# Connectors.net
KiCad netlist of a schematic drawn in Altium Designer
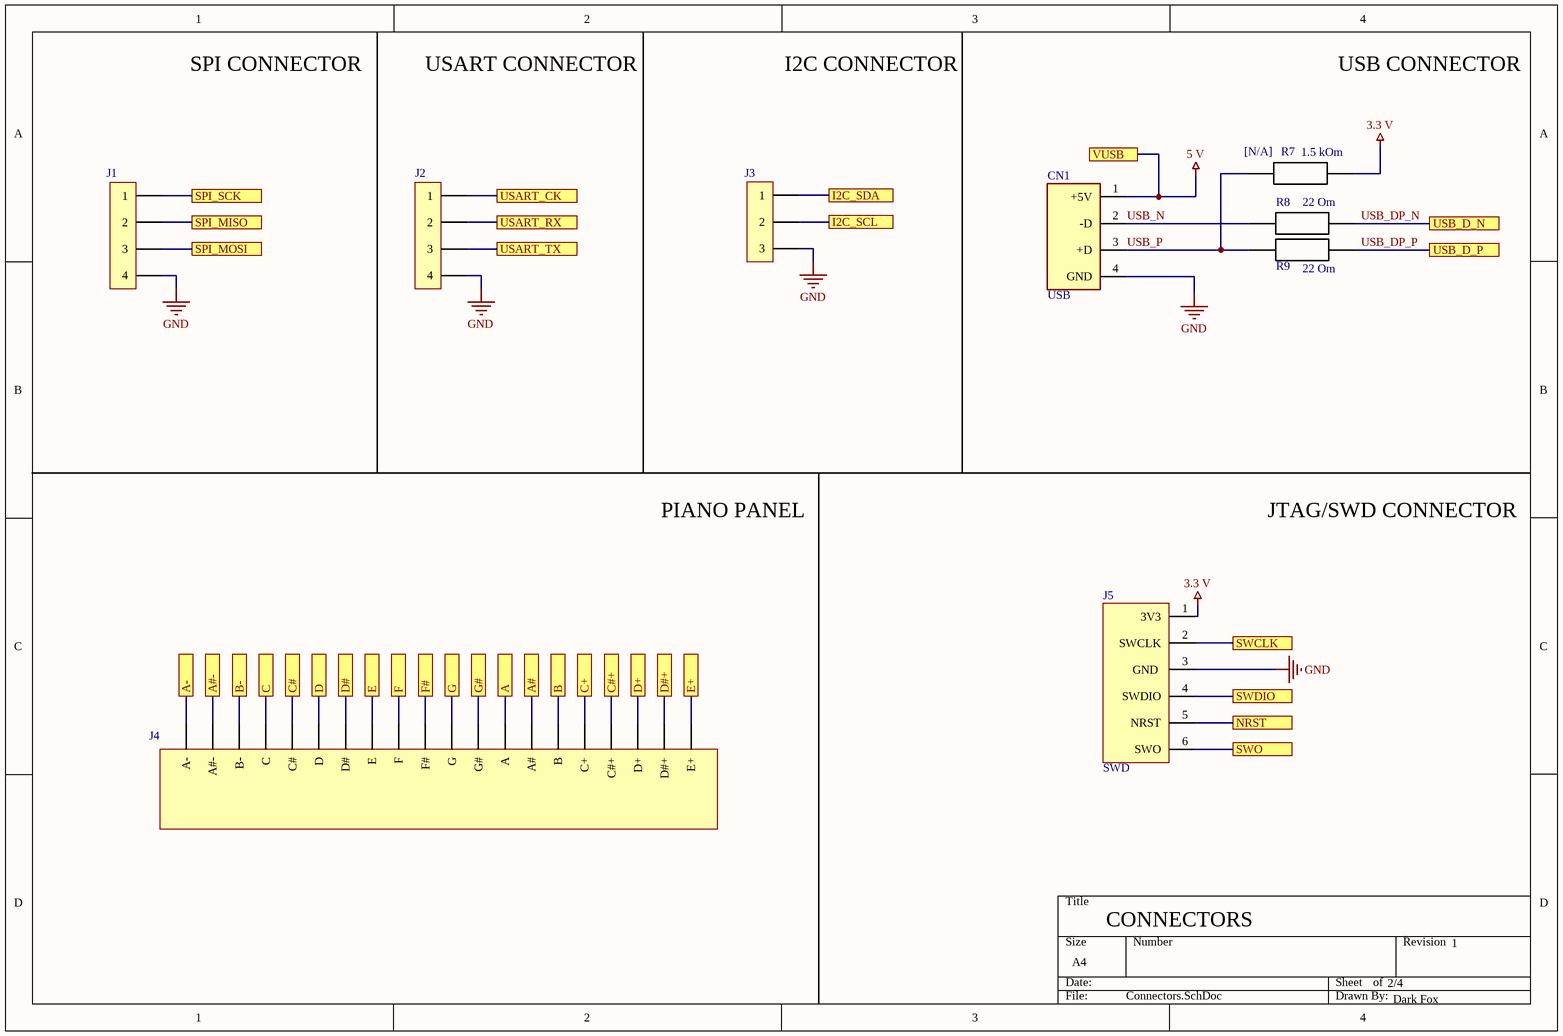
[diagram p0: Connectors.SchDoc]

(export (version "E")
  (design (tool "Eeschema 10.0.6"))
  (components
    (comp (ref "CN1") (value "USB") (footprint "USB") (libsource (lib "MyLib") (part "USB_2")))
    (comp (ref "J1") (value "4x2.54") (footprint "SMD 4x2.54") (libsource (lib "MyLib") (part "4x2.54")))
    (comp (ref "J2") (value "4x2.54") (footprint "SMD 4x2.54") (libsource (lib "MyLib") (part "4x2.54")))
    (comp (ref "J3") (value "3x2.54") (footprint "SMD 3x2.54") (libsource (lib "MyLib") (part "3x2.54")))
    (comp (ref "J4")
      (value "piano_full")
      (footprint "PIANO_FULL")
      (libsource (lib "MyLib") (part "piano_full"))
    )
    (comp (ref "J5") (value "SWD") (footprint "SWD_6_2.54") (libsource (lib "MyLib") (part "SWD")))
    (comp (ref "R7") (value "1.5 kOm") (footprint "1206") (libsource (lib "MyLib") (part "Res")))
    (comp (ref "R8") (value "22 Om") (footprint "1206") (libsource (lib "MyLib") (part "Res")))
    (comp (ref "R9") (value "22 Om") (footprint "1206") (libsource (lib "MyLib") (part "Res")))
  )
  (nets
    (net (code "1") (name "/A") (class "Default")
      (node (ref "J4") (pin "13") (pinfunction "A_13") (pintype "passive"))
    )
    (net (code "2") (name "/A#") (class "Default")
      (node (ref "J4") (pin "14") (pinfunction "A#_14") (pintype "passive"))
    )
    (net (code "3") (name "/A#-") (class "Default")
      (node (ref "J4") (pin "2") (pinfunction "A#-_2") (pintype "passive"))
    )
    (net (code "4") (name "/A-") (class "Default")
      (node (ref "J4") (pin "1") (pinfunction "A-_1") (pintype "passive"))
    )
    (net (code "5") (name "/B") (class "Default")
      (node (ref "J4") (pin "15") (pinfunction "B_15") (pintype "passive"))
    )
    (net (code "6") (name "/B-") (class "Default")
      (node (ref "J4") (pin "3") (pinfunction "B-_3") (pintype "passive"))
    )
    (net (code "7") (name "/C") (class "Default")
      (node (ref "J4") (pin "4") (pinfunction "C_4") (pintype "passive"))
    )
    (net (code "8") (name "/C#") (class "Default")
      (node (ref "J4") (pin "5") (pinfunction "C#_5") (pintype "passive"))
    )
    (net (code "9") (name "/C#+") (class "Default")
      (node (ref "J4") (pin "17") (pinfunction "C#+_17") (pintype "passive"))
    )
    (net (code "10") (name "/C+") (class "Default")
      (node (ref "J4") (pin "16") (pinfunction "C+_16") (pintype "passive"))
    )
    (net (code "11") (name "/D") (class "Default")
      (node (ref "J4") (pin "6") (pinfunction "D_6") (pintype "passive"))
    )
    (net (code "12") (name "/D#") (class "Default")
      (node (ref "J4") (pin "7") (pinfunction "D#_7") (pintype "passive"))
    )
    (net (code "13") (name "/D#+") (class "Default")
      (node (ref "J4") (pin "19") (pinfunction "D#+_19") (pintype "passive"))
    )
    (net (code "14") (name "/D+") (class "Default")
      (node (ref "J4") (pin "18") (pinfunction "D+_18") (pintype "passive"))
    )
    (net (code "15") (name "/E") (class "Default")
      (node (ref "J4") (pin "8") (pinfunction "E_8") (pintype "passive"))
    )
    (net (code "16") (name "/E+") (class "Default")
      (node (ref "J4") (pin "20") (pinfunction "E+_20") (pintype "passive"))
    )
    (net (code "17") (name "/F") (class "Default")
      (node (ref "J4") (pin "9") (pinfunction "F_9") (pintype "passive"))
    )
    (net (code "18") (name "/F#") (class "Default")
      (node (ref "J4") (pin "10") (pinfunction "F#_10") (pintype "passive"))
    )
    (net (code "19") (name "/G") (class "Default")
      (node (ref "J4") (pin "11") (pinfunction "G_11") (pintype "passive"))
    )
    (net (code "20") (name "/G#") (class "Default")
      (node (ref "J4") (pin "12") (pinfunction "G#_12") (pintype "passive"))
    )
    (net (code "21") (name "/I2C_SCL") (class "Default")
      (node (ref "J3") (pin "2") (pinfunction "2_2") (pintype "passive"))
    )
    (net (code "22") (name "/I2C_SDA") (class "Default")
      (node (ref "J3") (pin "1") (pinfunction "1_1") (pintype "passive"))
    )
    (net (code "23") (name "/NRST") (class "Default")
      (node (ref "J5") (pin "5") (pinfunction "NRST_5") (pintype "passive"))
    )
    (net (code "24") (name "/SPI_MISO") (class "Default")
      (node (ref "J1") (pin "2") (pinfunction "2_2") (pintype "passive"))
    )
    (net (code "25") (name "/SPI_MOSI") (class "Default")
      (node (ref "J1") (pin "3") (pinfunction "3_3") (pintype "passive"))
    )
    (net (code "26") (name "/SPI_SCK") (class "Default")
      (node (ref "J1") (pin "1") (pinfunction "1_1") (pintype "passive"))
    )
    (net (code "27") (name "/SWCLK") (class "Default")
      (node (ref "J5") (pin "2") (pinfunction "SWCLK_2") (pintype "passive"))
    )
    (net (code "28") (name "/SWDIO") (class "Default")
      (node (ref "J5") (pin "4") (pinfunction "SWDIO_4") (pintype "passive"))
    )
    (net (code "29") (name "/SWO") (class "Default")
      (node (ref "J5") (pin "6") (pinfunction "SWO_6") (pintype "passive"))
    )
    (net (code "30") (name "/USART_CK") (class "Default")
      (node (ref "J2") (pin "1") (pinfunction "1_1") (pintype "passive"))
    )
    (net (code "31") (name "/USART_RX") (class "Default")
      (node (ref "J2") (pin "2") (pinfunction "2_2") (pintype "passive"))
    )
    (net (code "32") (name "/USART_TX") (class "Default")
      (node (ref "J2") (pin "3") (pinfunction "3_3") (pintype "passive"))
    )
    (net (code "33") (name "/USB_DP_N") (class "Default")
      (node (ref "R8") (pin "2") (pinfunction "2_2") (pintype "passive"))
    )
    (net (code "34") (name "/USB_DP_P") (class "Default")
      (node (ref "R9") (pin "2") (pinfunction "2_2") (pintype "passive"))
    )
    (net (code "35") (name "/USB_N") (class "Default")
      (node (ref "CN1") (pin "2") (pinfunction "-D_2") (pintype "passive"))
      (node (ref "R8") (pin "1") (pinfunction "1_1") (pintype "passive"))
    )
    (net (code "36") (name "/USB_P") (class "Default")
      (node (ref "CN1") (pin "3") (pinfunction "+D_3") (pintype "passive"))
      (node (ref "R7") (pin "1") (pinfunction "1_1") (pintype "passive"))
      (node (ref "R9") (pin "1") (pinfunction "1_1") (pintype "passive"))
    )
    (net (code "37") (name "3.3 V") (class "Default")
      (node (ref "J5") (pin "1") (pinfunction "3V3_1") (pintype "passive"))
      (node (ref "R7") (pin "2") (pinfunction "2_2") (pintype "passive"))
    )
    (net (code "38") (name "5 V") (class "Default")
      (node (ref "CN1") (pin "1") (pinfunction "+5V_1") (pintype "power_in"))
    )
    (net (code "39") (name "GND") (class "Default")
      (node (ref "CN1") (pin "4") (pinfunction "GND_4") (pintype "passive"))
      (node (ref "J1") (pin "4") (pinfunction "4_4") (pintype "passive"))
      (node (ref "J2") (pin "4") (pinfunction "4_4") (pintype "passive"))
      (node (ref "J3") (pin "3") (pinfunction "3_3") (pintype "passive"))
      (node (ref "J5") (pin "3") (pinfunction "GND_3") (pintype "passive"))
    )
  )
)
